# ProPrj_Air_Purifier_ESP32C6_2026-05-01.net
KiCad netlist of a schematic drawn in EasyEDA Pro
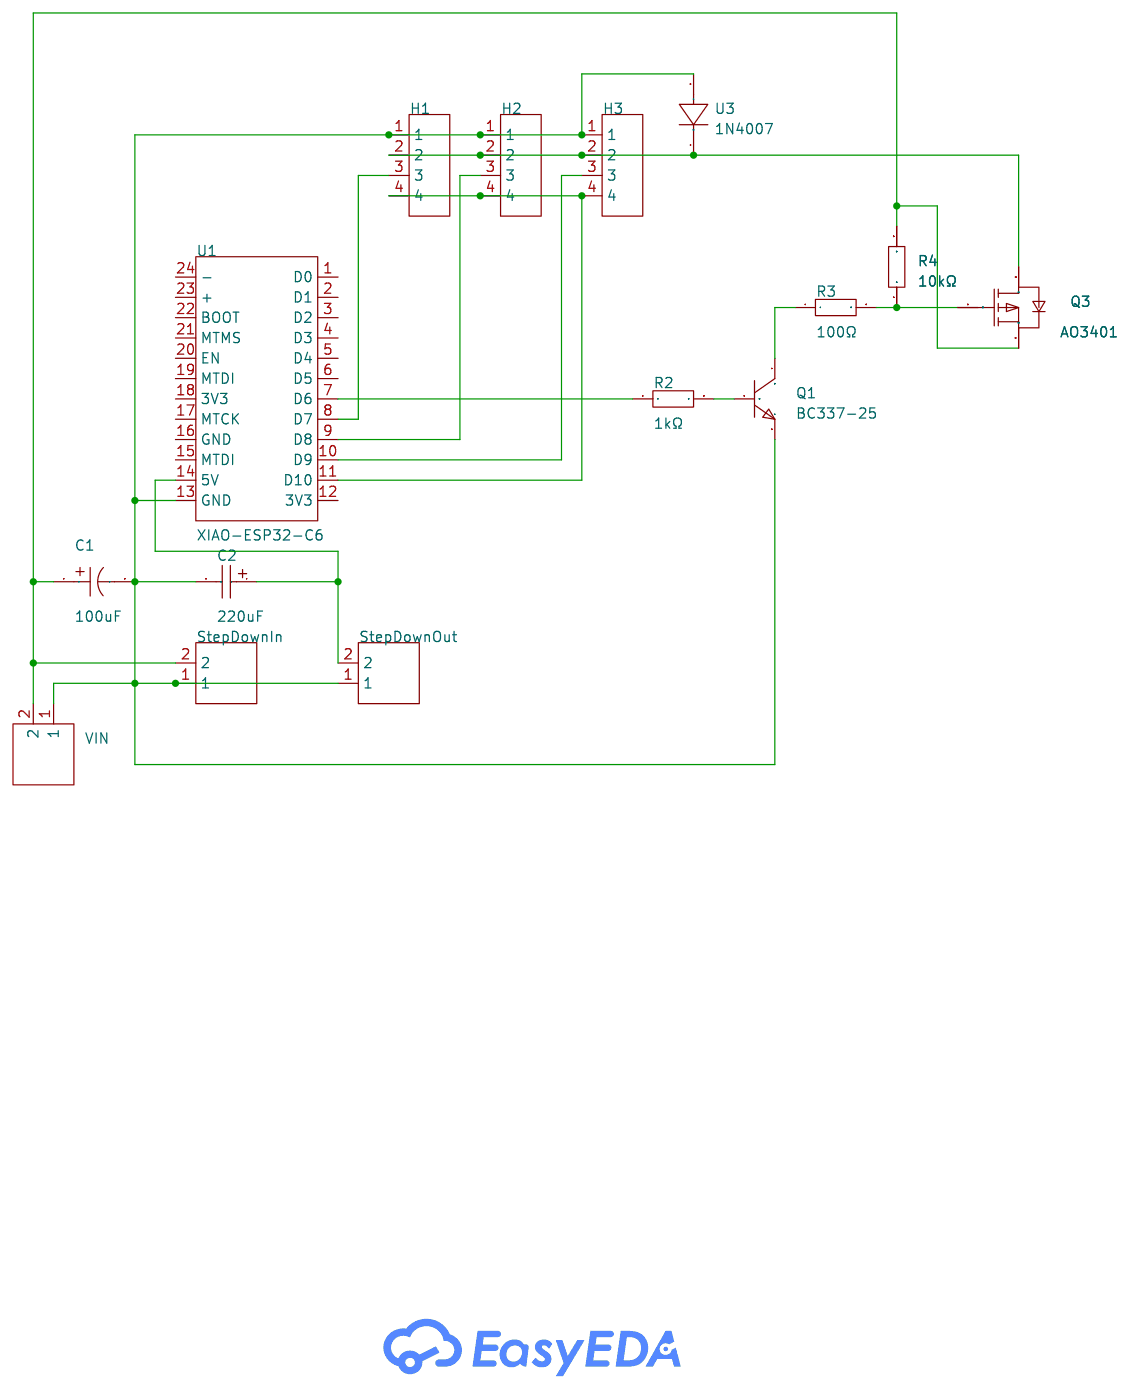
[diagram p0: schematic sheet]

(export (version "E")
  (design (tool "Eeschema 10.0.6"))
  (components
    (comp (ref "C1")
      (value "100uF")
      (footprint "easyedapro:CAP-SMD_BD6.3-L6.6-W6.6-RD")
      (fields (field (name "Manufacturer Part") "8101LDMAA07MH0001T") (field (name "Manufacturer") "FH(风华)"))
      (libsource (lib "easyedapro") (part "8101LDMAA07MH0001T"))
    )
    (comp (ref "C2")
      (value "220uF")
      (footprint "easyedapro:CASE-D_7343")
      (fields (field (name "Manufacturer Part") "TAJD227K010RNJ") (field (name "Manufacturer") "Kyocera AVX"))
      (libsource (lib "easyedapro") (part "TAJD227K010RNJ"))
    )
    (comp (ref "H1")
      (value "~")
      (footprint "easyedapro:HDR-TH_4P-P2.54-V-M")
      (libsource (lib "easyedapro") (part "PZ254V-11-04P"))
    )
    (comp (ref "H2")
      (value "~")
      (footprint "easyedapro:HDR-TH_4P-P2.54-V-M")
      (libsource (lib "easyedapro") (part "PZ254V-11-04P"))
    )
    (comp (ref "H3")
      (value "~")
      (footprint "easyedapro:HDR-TH_4P-P2.54-V-M")
      (libsource (lib "easyedapro") (part "PZ254V-11-04P"))
    )
    (comp (ref "Q1")
      (value "BC337-25")
      (footprint "easyedapro:TO-92-3_L4.9-W3.7-P1.27-L")
      (fields (field (name "Manufacturer") "LGE(鲁光)"))
      (libsource (lib "easyedapro") (part "BC337-25_C713610"))
    )
    (comp (ref "Q3")
      (value "AO3401")
      (footprint "easyedapro:SOT-23-3_L2.9-W1.3-P1.90-LS2.4-BR")
      (fields (field (name "Manufacturer") "YONGYUTAI(永裕泰)"))
      (libsource (lib "easyedapro") (part "AO3401_C6575062"))
    )
    (comp (ref "R2") (value "1kΩ") (footprint "easyedapro:R1206") (libsource (lib "easyedapro") (part "Res")))
    (comp (ref "R3")
      (value "100Ω")
      (footprint "easyedapro:R1206")
      (libsource (lib "easyedapro") (part "Res"))
    )
    (comp (ref "R4")
      (value "10kΩ")
      (footprint "easyedapro:R1206")
      (libsource (lib "easyedapro") (part "Res"))
    )
    (comp (ref "StepDownIn")
      (value "~")
      (footprint "easyedapro:HDR-TH_2P-P2.54-V-M-1")
      (libsource (lib "easyedapro") (part "210S-1*2P L=11.6MMGold-plated black"))
    )
    (comp (ref "StepDownOut")
      (value "~")
      (footprint "easyedapro:HDR-TH_2P-P2.54-V-M-1")
      (libsource (lib "easyedapro") (part "210S-1*2P L=11.6MMGold-plated black"))
    )
    (comp (ref "U1")
      (value "XIAO-ESP32-C6")
      (footprint "easyedapro:LCC-14P_L17.7-W20.8-XIAO-ESP32-C6")
      (libsource (lib "easyedapro") (part "XIAO-ESP32-C6"))
    )
    (comp (ref "U3")
      (value "1N4007")
      (footprint "easyedapro:DO-41_BD2.4-L4.7-P8.70-D0.6-RD")
      (fields (field (name "Manufacturer") "CJ(江苏长电/长晶)"))
      (libsource (lib "easyedapro") (part "1N4007_C5261026"))
    )
    (comp (ref "VIN")
      (value "~")
      (footprint "easyedapro:HDR-TH_2P-P2.54-V-M-1")
      (libsource (lib "easyedapro") (part "210S-1*2P L=11.6MMGold-plated black"))
    )
  )
  (nets
    (net (code "1") (name "Net-(Q1-B)") (class "Default")
      (node (ref "Q1") (pin "2") (pinfunction "B_2") (pintype "input"))
      (node (ref "R2") (pin "2") (pinfunction "2_2") (pintype "input"))
    )
    (net (code "2") (name "Net-(Q1-C)") (class "Default")
      (node (ref "Q1") (pin "1") (pinfunction "C_1") (pintype "input"))
      (node (ref "R3") (pin "1") (pinfunction "1_1") (pintype "input"))
    )
    (net (code "3") (name "Net-(Q1-E)") (class "Default")
      (node (ref "C1") (pin "2") (pinfunction "2_2") (pintype "input"))
      (node (ref "C2") (pin "2") (pinfunction "2_2") (pintype "input"))
      (node (ref "H1") (pin "1") (pinfunction "1_1") (pintype "unspecified"))
      (node (ref "H2") (pin "1") (pinfunction "1_1") (pintype "unspecified"))
      (node (ref "H3") (pin "1") (pinfunction "1_1") (pintype "unspecified"))
      (node (ref "Q1") (pin "3") (pinfunction "E_3") (pintype "input"))
      (node (ref "StepDownIn") (pin "1") (pinfunction "1_1") (pintype "unspecified"))
      (node (ref "StepDownOut") (pin "1") (pinfunction "1_1") (pintype "unspecified"))
      (node (ref "U1") (pin "13") (pinfunction "GND_13") (pintype "unspecified"))
      (node (ref "U3") (pin "2") (pinfunction "A_2") (pintype "unspecified"))
      (node (ref "VIN") (pin "1") (pinfunction "1_1") (pintype "unspecified"))
    )
    (net (code "4") (name "Net-(Q3-D)") (class "Default")
      (node (ref "H1") (pin "2") (pinfunction "2_2") (pintype "unspecified"))
      (node (ref "H2") (pin "2") (pinfunction "2_2") (pintype "unspecified"))
      (node (ref "H3") (pin "2") (pinfunction "2_2") (pintype "unspecified"))
      (node (ref "Q3") (pin "3") (pinfunction "D_3") (pintype "unspecified"))
      (node (ref "U3") (pin "1") (pinfunction "C_1") (pintype "unspecified"))
    )
    (net (code "5") (name "Net-(Q3-G)") (class "Default")
      (node (ref "Q3") (pin "1") (pinfunction "G_1") (pintype "unspecified"))
      (node (ref "R3") (pin "2") (pinfunction "2_2") (pintype "input"))
      (node (ref "R4") (pin "1") (pinfunction "1_1") (pintype "input"))
    )
    (net (code "6") (name "Net-(Q3-S)") (class "Default")
      (node (ref "C1") (pin "1") (pinfunction "1_1") (pintype "input"))
      (node (ref "Q3") (pin "2") (pinfunction "S_2") (pintype "unspecified"))
      (node (ref "R4") (pin "2") (pinfunction "2_2") (pintype "input"))
      (node (ref "StepDownIn") (pin "2") (pinfunction "2_2") (pintype "unspecified"))
      (node (ref "VIN") (pin "2") (pinfunction "2_2") (pintype "unspecified"))
    )
    (net (code "7") (name "Net-(U1-5V)") (class "Default")
      (node (ref "C2") (pin "1") (pinfunction "1_1") (pintype "input"))
      (node (ref "StepDownOut") (pin "2") (pinfunction "2_2") (pintype "unspecified"))
      (node (ref "U1") (pin "14") (pinfunction "5V_14") (pintype "unspecified"))
    )
    (net (code "8") (name "Net-(U1-D6)") (class "Default")
      (node (ref "R2") (pin "1") (pinfunction "1_1") (pintype "input"))
      (node (ref "U1") (pin "7") (pinfunction "D6_7") (pintype "unspecified"))
    )
    (net (code "9") (name "Net-(U1-D7)") (class "Default")
      (node (ref "H1") (pin "3") (pinfunction "3_3") (pintype "unspecified"))
      (node (ref "U1") (pin "8") (pinfunction "D7_8") (pintype "unspecified"))
    )
    (net (code "10") (name "Net-(U1-D8)") (class "Default")
      (node (ref "H2") (pin "3") (pinfunction "3_3") (pintype "unspecified"))
      (node (ref "U1") (pin "9") (pinfunction "D8_9") (pintype "unspecified"))
    )
    (net (code "11") (name "Net-(U1-D9)") (class "Default")
      (node (ref "H3") (pin "3") (pinfunction "3_3") (pintype "unspecified"))
      (node (ref "U1") (pin "10") (pinfunction "D9_10") (pintype "unspecified"))
    )
    (net (code "12") (name "Net-(U1-D10)") (class "Default")
      (node (ref "H1") (pin "4") (pinfunction "4_4") (pintype "unspecified"))
      (node (ref "H2") (pin "4") (pinfunction "4_4") (pintype "unspecified"))
      (node (ref "H3") (pin "4") (pinfunction "4_4") (pintype "unspecified"))
      (node (ref "U1") (pin "11") (pinfunction "D10_11") (pintype "unspecified"))
    )
    (net (code "13") (name "unconnected-(U1-+-Pad23)") (class "Default")
      (node (ref "U1") (pin "23") (pinfunction "+_23") (pintype "unspecified"))
    )
    (net (code "14") (name "unconnected-(U1---Pad24)") (class "Default")
      (node (ref "U1") (pin "24") (pinfunction "-_24") (pintype "unspecified"))
    )
    (net (code "15") (name "unconnected-(U1-3V3-Pad12)") (class "Default")
      (node (ref "U1") (pin "12") (pinfunction "3V3_12") (pintype "unspecified"))
    )
    (net (code "16") (name "unconnected-(U1-3V3-Pad18)") (class "Default")
      (node (ref "U1") (pin "18") (pinfunction "3V3_18") (pintype "unspecified"))
    )
    (net (code "17") (name "unconnected-(U1-BOOT-Pad22)") (class "Default")
      (node (ref "U1") (pin "22") (pinfunction "BOOT_22") (pintype "unspecified"))
    )
    (net (code "18") (name "unconnected-(U1-D0-Pad1)") (class "Default")
      (node (ref "U1") (pin "1") (pinfunction "D0_1") (pintype "unspecified"))
    )
    (net (code "19") (name "unconnected-(U1-D1-Pad2)") (class "Default")
      (node (ref "U1") (pin "2") (pinfunction "D1_2") (pintype "unspecified"))
    )
    (net (code "20") (name "unconnected-(U1-D2-Pad3)") (class "Default")
      (node (ref "U1") (pin "3") (pinfunction "D2_3") (pintype "unspecified"))
    )
    (net (code "21") (name "unconnected-(U1-D3-Pad4)") (class "Default")
      (node (ref "U1") (pin "4") (pinfunction "D3_4") (pintype "unspecified"))
    )
    (net (code "22") (name "unconnected-(U1-D4-Pad5)") (class "Default")
      (node (ref "U1") (pin "5") (pinfunction "D4_5") (pintype "unspecified"))
    )
    (net (code "23") (name "unconnected-(U1-D5-Pad6)") (class "Default")
      (node (ref "U1") (pin "6") (pinfunction "D5_6") (pintype "unspecified"))
    )
    (net (code "24") (name "unconnected-(U1-EN-Pad20)") (class "Default")
      (node (ref "U1") (pin "20") (pinfunction "EN_20") (pintype "unspecified"))
    )
    (net (code "25") (name "unconnected-(U1-GND-Pad16)") (class "Default")
      (node (ref "U1") (pin "16") (pinfunction "GND_16") (pintype "unspecified"))
    )
    (net (code "26") (name "unconnected-(U1-MTCK-Pad17)") (class "Default")
      (node (ref "U1") (pin "17") (pinfunction "MTCK_17") (pintype "unspecified"))
    )
    (net (code "27") (name "unconnected-(U1-MTDI-Pad15)") (class "Default")
      (node (ref "U1") (pin "15") (pinfunction "MTDI_15") (pintype "unspecified"))
    )
    (net (code "28") (name "unconnected-(U1-MTDI-Pad19)") (class "Default")
      (node (ref "U1") (pin "19") (pinfunction "MTDI_19") (pintype "unspecified"))
    )
    (net (code "29") (name "unconnected-(U1-MTMS-Pad21)") (class "Default")
      (node (ref "U1") (pin "21") (pinfunction "MTMS_21") (pintype "unspecified"))
    )
  )
)
